# BCI_Module.net
KiCad netlist of a schematic drawn in EAGLE
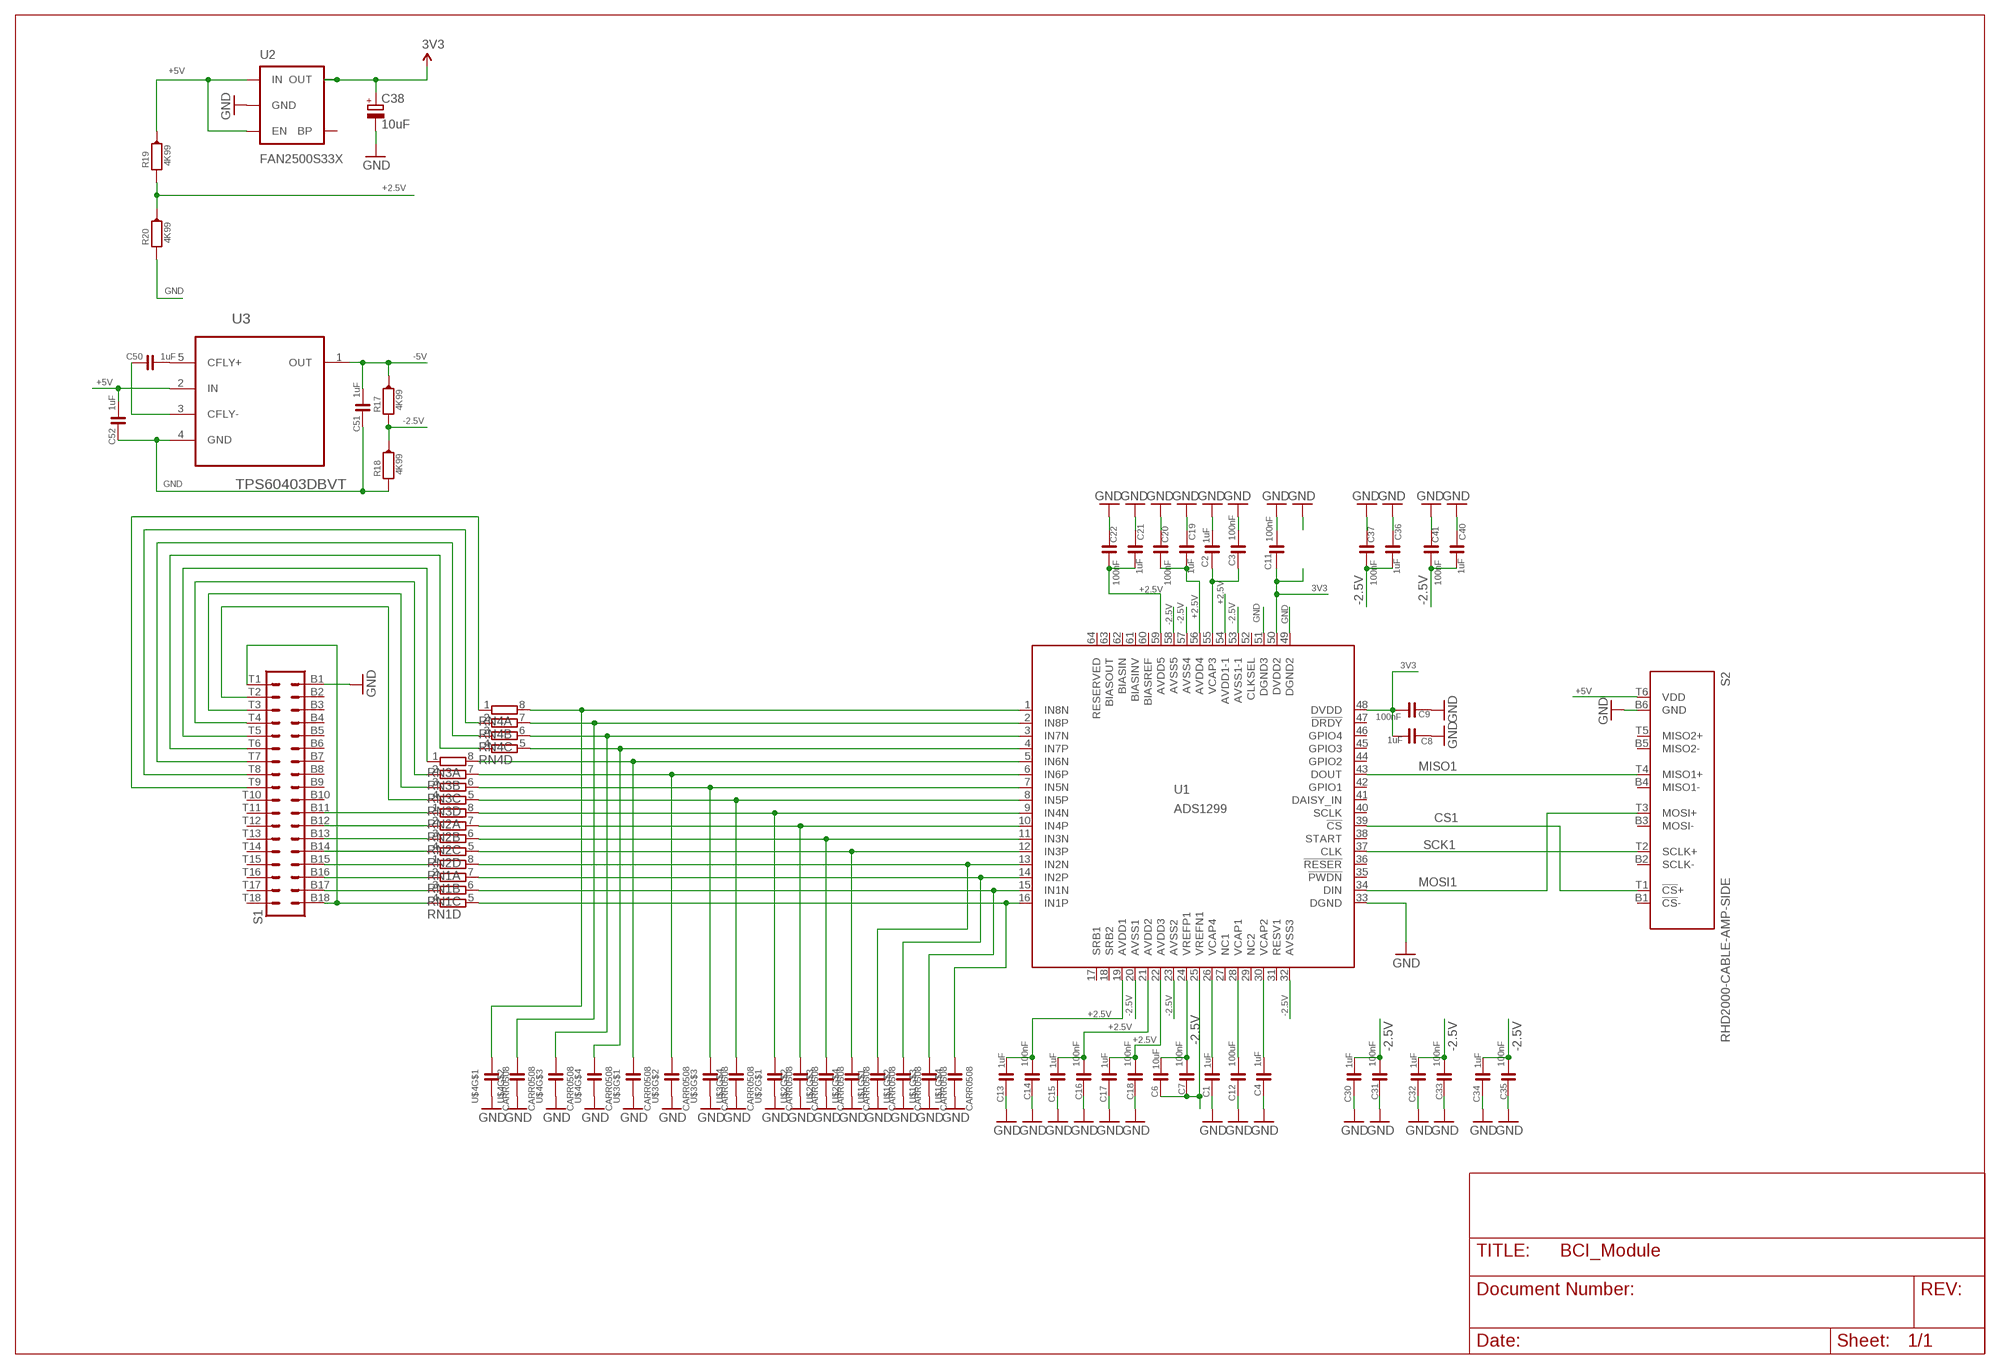
[diagram p0: schematic, sheet 1]

(export (version "E")
  (design (tool "Eeschema 10.0.6"))
  (components
    (comp (ref "C1")
      (value "1uF")
      (footprint "eagle-import:0603_R")
      (libsource (lib "eagle-import") (part "C0603_R"))
    )
    (comp (ref "C2")
      (value "1uF")
      (footprint "eagle-import:0603_R")
      (libsource (lib "eagle-import") (part "C0603_R"))
    )
    (comp (ref "C3")
      (value "100nF")
      (footprint "eagle-import:0402_R")
      (libsource (lib "eagle-import") (part "C0402_R"))
    )
    (comp (ref "C4")
      (value "1uF")
      (footprint "eagle-import:0603_R")
      (libsource (lib "eagle-import") (part "C0603_R"))
    )
    (comp (ref "C6")
      (value "10uF")
      (footprint "eagle-import:0603_R")
      (libsource (lib "eagle-import") (part "C0603_R"))
    )
    (comp (ref "C7")
      (value "100nF")
      (footprint "eagle-import:0402_R")
      (libsource (lib "eagle-import") (part "C0402_R"))
    )
    (comp (ref "C8")
      (value "1uF")
      (footprint "eagle-import:0603_R")
      (libsource (lib "eagle-import") (part "C0603_R"))
    )
    (comp (ref "C9")
      (value "100nF")
      (footprint "eagle-import:0402_R")
      (libsource (lib "eagle-import") (part "C0402_R"))
    )
    (comp (ref "C11")
      (value "100nF")
      (footprint "eagle-import:0402_R")
      (libsource (lib "eagle-import") (part "C0402_R"))
    )
    (comp (ref "C12")
      (value "100uF")
      (footprint "eagle-import:1206_R")
      (libsource (lib "eagle-import") (part "C1206_R"))
    )
    (comp (ref "C13")
      (value "1uF")
      (footprint "eagle-import:0603_R")
      (libsource (lib "eagle-import") (part "C0603_R"))
    )
    (comp (ref "C14")
      (value "100nF")
      (footprint "eagle-import:0402_R")
      (libsource (lib "eagle-import") (part "C0402_R"))
    )
    (comp (ref "C15")
      (value "1uF")
      (footprint "eagle-import:0603_R")
      (libsource (lib "eagle-import") (part "C0603_R"))
    )
    (comp (ref "C16")
      (value "100nF")
      (footprint "eagle-import:0402_R")
      (libsource (lib "eagle-import") (part "C0402_R"))
    )
    (comp (ref "C17")
      (value "1uF")
      (footprint "eagle-import:0603_R")
      (libsource (lib "eagle-import") (part "C0603_R"))
    )
    (comp (ref "C18")
      (value "100nF")
      (footprint "eagle-import:0402_R")
      (libsource (lib "eagle-import") (part "C0402_R"))
    )
    (comp (ref "C19")
      (value "1uF")
      (footprint "eagle-import:0603_R")
      (libsource (lib "eagle-import") (part "C0603_R"))
    )
    (comp (ref "C20")
      (value "100nF")
      (footprint "eagle-import:0402_R")
      (libsource (lib "eagle-import") (part "C0402_R"))
    )
    (comp (ref "C21")
      (value "1uF")
      (footprint "eagle-import:0603_R")
      (libsource (lib "eagle-import") (part "C0603_R"))
    )
    (comp (ref "C22")
      (value "100nF")
      (footprint "eagle-import:0402_R")
      (libsource (lib "eagle-import") (part "C0402_R"))
    )
    (comp (ref "C30")
      (value "1uF")
      (footprint "eagle-import:0603_R")
      (libsource (lib "eagle-import") (part "C0603_R"))
    )
    (comp (ref "C31")
      (value "100nF")
      (footprint "eagle-import:0402_R")
      (libsource (lib "eagle-import") (part "C0402_R"))
    )
    (comp (ref "C32")
      (value "1uF")
      (footprint "eagle-import:0603_R")
      (libsource (lib "eagle-import") (part "C0603_R"))
    )
    (comp (ref "C33")
      (value "100nF")
      (footprint "eagle-import:0402_R")
      (libsource (lib "eagle-import") (part "C0402_R"))
    )
    (comp (ref "C34")
      (value "1uF")
      (footprint "eagle-import:0603_R")
      (libsource (lib "eagle-import") (part "C0603_R"))
    )
    (comp (ref "C35")
      (value "100nF")
      (footprint "eagle-import:0402_R")
      (libsource (lib "eagle-import") (part "C0402_R"))
    )
    (comp (ref "C36")
      (value "1uF")
      (footprint "eagle-import:0603_R")
      (libsource (lib "eagle-import") (part "C0603_R"))
    )
    (comp (ref "C37")
      (value "100nF")
      (footprint "eagle-import:0402_R")
      (libsource (lib "eagle-import") (part "C0402_R"))
    )
    (comp (ref "C38")
      (value "10uF")
      (footprint "eagle-import:R_2012-12R")
      (libsource (lib "eagle-import") (part "CPOL-EUR/2012-12R"))
    )
    (comp (ref "C40")
      (value "1uF")
      (footprint "eagle-import:0603_R")
      (libsource (lib "eagle-import") (part "C0603_R"))
    )
    (comp (ref "C41")
      (value "100nF")
      (footprint "eagle-import:0402_R")
      (libsource (lib "eagle-import") (part "C0402_R"))
    )
    (comp (ref "C50")
      (value "1uF")
      (footprint "eagle-import:0603_R")
      (libsource (lib "eagle-import") (part "C0603_R"))
    )
    (comp (ref "C51")
      (value "1uF")
      (footprint "eagle-import:0603_R")
      (libsource (lib "eagle-import") (part "C0603_R"))
    )
    (comp (ref "C52")
      (value "1uF")
      (footprint "eagle-import:0603_R")
      (libsource (lib "eagle-import") (part "C0603_R"))
    )
    (comp (ref "R17")
      (value "4K99")
      (footprint "eagle-import:0402_R@1")
      (libsource (lib "eagle-import") (part "R0402_R"))
    )
    (comp (ref "R18")
      (value "4K99")
      (footprint "eagle-import:0402_R@1")
      (libsource (lib "eagle-import") (part "R0402_R"))
    )
    (comp (ref "R19")
      (value "4K99")
      (footprint "eagle-import:0402_R@1")
      (libsource (lib "eagle-import") (part "R0402_R"))
    )
    (comp (ref "R20")
      (value "4K99")
      (footprint "eagle-import:0402_R@1")
      (libsource (lib "eagle-import") (part "R0402_R"))
    )
    (comp (ref "RN1")
      (value "4R-NYC124")
      (footprint "eagle-import:YC124")
      (libsource (lib "eagle-import") (part "4R-NYC124"))
    )
    (comp (ref "RN2")
      (value "4R-NYC124")
      (footprint "eagle-import:YC124")
      (libsource (lib "eagle-import") (part "4R-NYC124"))
    )
    (comp (ref "RN3")
      (value "4R-NYC124")
      (footprint "eagle-import:YC124")
      (libsource (lib "eagle-import") (part "4R-NYC124"))
    )
    (comp (ref "RN4")
      (value "4R-NYC124")
      (footprint "eagle-import:YC124")
      (libsource (lib "eagle-import") (part "4R-NYC124"))
    )
    (comp (ref "S1")
      (value "OMNETICS_A79025")
      (footprint "eagle-import:OMNETICS_A79025")
      (libsource (lib "eagle-import") (part "OMNETICS_A79025"))
    )
    (comp (ref "S2")
      (value "RHD2000-CABLE-AMP-SIDE")
      (footprint "eagle-import:OMNETICS_PZN-12-AA")
      (libsource (lib "eagle-import") (part "RHD2000-CABLE-AMP-SIDE"))
    )
    (comp (ref "U$1")
      (value "CARR0508")
      (footprint "eagle-import:CARR0508")
      (libsource (lib "eagle-import") (part "CARR0508"))
    )
    (comp (ref "U$2")
      (value "CARR0508")
      (footprint "eagle-import:CARR0508")
      (libsource (lib "eagle-import") (part "CARR0508"))
    )
    (comp (ref "U$3")
      (value "CARR0508")
      (footprint "eagle-import:CARR0508")
      (libsource (lib "eagle-import") (part "CARR0508"))
    )
    (comp (ref "U$4")
      (value "CARR0508")
      (footprint "eagle-import:CARR0508")
      (libsource (lib "eagle-import") (part "CARR0508"))
    )
    (comp (ref "U1")
      (value "ADS1299")
      (footprint "eagle-import:SQFP-S-10X10-64")
      (libsource (lib "eagle-import") (part "ADS1299"))
    )
    (comp (ref "U2")
      (value "FAN2500S33X")
      (footprint "eagle-import:SOT23-5$2")
      (libsource (lib "eagle-import") (part "V_REG_LDOSMD"))
    )
    (comp (ref "U3")
      (value "TPS60403DBVT")
      (footprint "eagle-import:SOT95P280X145-5N")
      (libsource (lib "eagle-import") (part "TPS60403DBVT"))
    )
  )
  (nets
    (net (code "1") (name "/+2.5V") (class "Default")
      (node (ref "C13") (pin "1") (pinfunction "1_1") (pintype "bidirectional"))
      (node (ref "C14") (pin "1") (pinfunction "1_1") (pintype "bidirectional"))
      (node (ref "C15") (pin "1") (pinfunction "1_1") (pintype "bidirectional"))
      (node (ref "C16") (pin "1") (pinfunction "1_1") (pintype "bidirectional"))
      (node (ref "C17") (pin "1") (pinfunction "1_1") (pintype "bidirectional"))
      (node (ref "C18") (pin "1") (pinfunction "1_1") (pintype "bidirectional"))
      (node (ref "C19") (pin "1") (pinfunction "1_1") (pintype "bidirectional"))
      (node (ref "C20") (pin "1") (pinfunction "1_1") (pintype "bidirectional"))
      (node (ref "C21") (pin "1") (pinfunction "1_1") (pintype "bidirectional"))
      (node (ref "C22") (pin "1") (pinfunction "1_1") (pintype "bidirectional"))
      (node (ref "R19") (pin "2") (pinfunction "2_2") (pintype "bidirectional"))
      (node (ref "R20") (pin "1") (pinfunction "1_1") (pintype "bidirectional"))
      (node (ref "U1") (pin "19") (pinfunction "AVDD1_19") (pintype "output"))
      (node (ref "U1") (pin "21") (pinfunction "AVDD2_21") (pintype "power_in"))
      (node (ref "U1") (pin "22") (pinfunction "AVDD3_22") (pintype "power_in"))
      (node (ref "U1") (pin "54") (pinfunction "AVDD1-1_54") (pintype "power_in"))
      (node (ref "U1") (pin "56") (pinfunction "AVDD4_56") (pintype "input"))
      (node (ref "U1") (pin "59") (pinfunction "AVDD5_59") (pintype "power_in"))
    )
    (net (code "2") (name "/+5V") (class "Default")
      (node (ref "C52") (pin "1") (pinfunction "1_1") (pintype "bidirectional"))
      (node (ref "R19") (pin "1") (pinfunction "1_1") (pintype "bidirectional"))
      (node (ref "S2") (pin "T6") (pinfunction "VDD_T6") (pintype "bidirectional"))
      (node (ref "U2") (pin "1") (pinfunction "IN_1") (pintype "input"))
      (node (ref "U2") (pin "3") (pinfunction "EN_3") (pintype "input"))
      (node (ref "U3") (pin "2") (pinfunction "IN_2") (pintype "power_in"))
    )
    (net (code "3") (name "/-2.5V") (class "Default")
      (node (ref "C30") (pin "1") (pinfunction "1_1") (pintype "bidirectional"))
      (node (ref "C31") (pin "1") (pinfunction "1_1") (pintype "bidirectional"))
      (node (ref "C32") (pin "1") (pinfunction "1_1") (pintype "bidirectional"))
      (node (ref "C33") (pin "1") (pinfunction "1_1") (pintype "bidirectional"))
      (node (ref "C34") (pin "1") (pinfunction "1_1") (pintype "bidirectional"))
      (node (ref "C35") (pin "1") (pinfunction "1_1") (pintype "bidirectional"))
      (node (ref "C36") (pin "1") (pinfunction "1_1") (pintype "bidirectional"))
      (node (ref "C37") (pin "1") (pinfunction "1_1") (pintype "bidirectional"))
      (node (ref "C40") (pin "1") (pinfunction "1_1") (pintype "bidirectional"))
      (node (ref "C41") (pin "1") (pinfunction "1_1") (pintype "bidirectional"))
      (node (ref "C6") (pin "2") (pinfunction "2_2") (pintype "bidirectional"))
      (node (ref "C7") (pin "2") (pinfunction "2_2") (pintype "bidirectional"))
      (node (ref "R17") (pin "2") (pinfunction "2_2") (pintype "bidirectional"))
      (node (ref "R18") (pin "1") (pinfunction "1_1") (pintype "bidirectional"))
      (node (ref "U1") (pin "20") (pinfunction "AVSS1_20") (pintype "output"))
      (node (ref "U1") (pin "23") (pinfunction "AVSS2_23") (pintype "power_in"))
      (node (ref "U1") (pin "25") (pinfunction "VREFN1_25") (pintype "power_in"))
      (node (ref "U1") (pin "32") (pinfunction "AVSS3_32") (pintype "input"))
      (node (ref "U1") (pin "53") (pinfunction "AVSS1-1_53") (pintype "power_in"))
      (node (ref "U1") (pin "57") (pinfunction "AVSS4_57") (pintype "input"))
      (node (ref "U1") (pin "58") (pinfunction "AVSS5_58") (pintype "power_in"))
    )
    (net (code "4") (name "/-5V") (class "Default")
      (node (ref "C51") (pin "1") (pinfunction "1_1") (pintype "bidirectional"))
      (node (ref "R17") (pin "1") (pinfunction "1_1") (pintype "bidirectional"))
      (node (ref "U3") (pin "1") (pinfunction "OUT_1") (pintype "output"))
    )
    (net (code "5") (name "/BIASREF") (class "Default")
      (node (ref "U1") (pin "60") (pinfunction "BIASREF_60") (pintype "power_in"))
    )
    (net (code "6") (name "/CS1") (class "Default")
      (node (ref "S2") (pin "T1") (pinfunction "~{CS}+_T1") (pintype "bidirectional"))
      (node (ref "U1") (pin "39") (pinfunction "~{CS}_39") (pintype "input"))
    )
    (net (code "7") (name "/GPIO2") (class "Default")
      (node (ref "U1") (pin "44") (pinfunction "GPIO2_44") (pintype "power_in"))
    )
    (net (code "8") (name "/MISO1") (class "Default")
      (node (ref "S2") (pin "T4") (pinfunction "MISO1+_T4") (pintype "bidirectional"))
      (node (ref "U1") (pin "43") (pinfunction "DOUT_43") (pintype "power_in"))
    )
    (net (code "9") (name "/MOSI1") (class "Default")
      (node (ref "S2") (pin "T3") (pinfunction "MOSI+_T3") (pintype "bidirectional"))
      (node (ref "U1") (pin "34") (pinfunction "DIN_34") (pintype "input"))
    )
    (net (code "10") (name "/SCK1") (class "Default")
      (node (ref "S2") (pin "T2") (pinfunction "SCLK+_T2") (pintype "bidirectional"))
      (node (ref "U1") (pin "37") (pinfunction "CLK_37") (pintype "input"))
    )
    (net (code "11") (name "3V3") (class "Default")
      (node (ref "C11") (pin "1") (pinfunction "1_1") (pintype "bidirectional"))
      (node (ref "C38") (pin "+") (pinfunction "+_+") (pintype "passive"))
      (node (ref "C8") (pin "1") (pinfunction "1_1") (pintype "bidirectional"))
      (node (ref "C9") (pin "1") (pinfunction "1_1") (pintype "bidirectional"))
      (node (ref "U1") (pin "48") (pinfunction "DVDD_48") (pintype "input"))
      (node (ref "U1") (pin "50") (pinfunction "DVDD2_50") (pintype "input"))
      (node (ref "U2") (pin "5") (pinfunction "OUT_5") (pintype "passive"))
    )
    (net (code "12") (name "GND") (class "Default")
      (node (ref "C1") (pin "2") (pinfunction "2_2") (pintype "bidirectional"))
      (node (ref "C11") (pin "2") (pinfunction "2_2") (pintype "bidirectional"))
      (node (ref "C12") (pin "2") (pinfunction "2_2") (pintype "bidirectional"))
      (node (ref "C13") (pin "2") (pinfunction "2_2") (pintype "bidirectional"))
      (node (ref "C14") (pin "2") (pinfunction "2_2") (pintype "bidirectional"))
      (node (ref "C15") (pin "2") (pinfunction "2_2") (pintype "bidirectional"))
      (node (ref "C16") (pin "2") (pinfunction "2_2") (pintype "bidirectional"))
      (node (ref "C17") (pin "2") (pinfunction "2_2") (pintype "bidirectional"))
      (node (ref "C18") (pin "2") (pinfunction "2_2") (pintype "bidirectional"))
      (node (ref "C19") (pin "2") (pinfunction "2_2") (pintype "bidirectional"))
      (node (ref "C2") (pin "2") (pinfunction "2_2") (pintype "bidirectional"))
      (node (ref "C20") (pin "2") (pinfunction "2_2") (pintype "bidirectional"))
      (node (ref "C21") (pin "2") (pinfunction "2_2") (pintype "bidirectional"))
      (node (ref "C22") (pin "2") (pinfunction "2_2") (pintype "bidirectional"))
      (node (ref "C3") (pin "2") (pinfunction "2_2") (pintype "bidirectional"))
      (node (ref "C30") (pin "2") (pinfunction "2_2") (pintype "bidirectional"))
      (node (ref "C31") (pin "2") (pinfunction "2_2") (pintype "bidirectional"))
      (node (ref "C32") (pin "2") (pinfunction "2_2") (pintype "bidirectional"))
      (node (ref "C33") (pin "2") (pinfunction "2_2") (pintype "bidirectional"))
      (node (ref "C34") (pin "2") (pinfunction "2_2") (pintype "bidirectional"))
      (node (ref "C35") (pin "2") (pinfunction "2_2") (pintype "bidirectional"))
      (node (ref "C36") (pin "2") (pinfunction "2_2") (pintype "bidirectional"))
      (node (ref "C37") (pin "2") (pinfunction "2_2") (pintype "bidirectional"))
      (node (ref "C38") (pin "-") (pinfunction "-_-") (pintype "passive"))
      (node (ref "C4") (pin "2") (pinfunction "2_2") (pintype "bidirectional"))
      (node (ref "C40") (pin "2") (pinfunction "2_2") (pintype "bidirectional"))
      (node (ref "C41") (pin "2") (pinfunction "2_2") (pintype "bidirectional"))
      (node (ref "C51") (pin "2") (pinfunction "2_2") (pintype "bidirectional"))
      (node (ref "C52") (pin "2") (pinfunction "2_2") (pintype "bidirectional"))
      (node (ref "C8") (pin "2") (pinfunction "2_2") (pintype "bidirectional"))
      (node (ref "C9") (pin "2") (pinfunction "2_2") (pintype "bidirectional"))
      (node (ref "R18") (pin "2") (pinfunction "2_2") (pintype "bidirectional"))
      (node (ref "R20") (pin "2") (pinfunction "2_2") (pintype "bidirectional"))
      (node (ref "S1") (pin "B1") (pinfunction "B1_B1") (pintype "passive"))
      (node (ref "S2") (pin "B6") (pinfunction "GND_B6") (pintype "power_in"))
      (node (ref "U$1") (pin "P$2") (pinfunction "2_P$2") (pintype "bidirectional"))
      (node (ref "U$1") (pin "P$4") (pinfunction "2_P$4") (pintype "bidirectional"))
      (node (ref "U$1") (pin "P$6") (pinfunction "2_P$6") (pintype "bidirectional"))
      (node (ref "U$1") (pin "P$8") (pinfunction "2_P$8") (pintype "bidirectional"))
      (node (ref "U$2") (pin "P$2") (pinfunction "2_P$2") (pintype "bidirectional"))
      (node (ref "U$2") (pin "P$4") (pinfunction "2_P$4") (pintype "bidirectional"))
      (node (ref "U$2") (pin "P$6") (pinfunction "2_P$6") (pintype "bidirectional"))
      (node (ref "U$2") (pin "P$8") (pinfunction "2_P$8") (pintype "bidirectional"))
      (node (ref "U$3") (pin "P$2") (pinfunction "2_P$2") (pintype "bidirectional"))
      (node (ref "U$3") (pin "P$4") (pinfunction "2_P$4") (pintype "bidirectional"))
      (node (ref "U$3") (pin "P$6") (pinfunction "2_P$6") (pintype "bidirectional"))
      (node (ref "U$3") (pin "P$8") (pinfunction "2_P$8") (pintype "bidirectional"))
      (node (ref "U$4") (pin "P$2") (pinfunction "2_P$2") (pintype "bidirectional"))
      (node (ref "U$4") (pin "P$4") (pinfunction "2_P$4") (pintype "bidirectional"))
      (node (ref "U$4") (pin "P$6") (pinfunction "2_P$6") (pintype "bidirectional"))
      (node (ref "U$4") (pin "P$8") (pinfunction "2_P$8") (pintype "bidirectional"))
      (node (ref "U1") (pin "33") (pinfunction "DGND_33") (pintype "input"))
      (node (ref "U1") (pin "49") (pinfunction "DGND2_49") (pintype "input"))
      (node (ref "U1") (pin "51") (pinfunction "DGND3_51") (pintype "input"))
      (node (ref "U2") (pin "2") (pinfunction "GND_2") (pintype "input"))
      (node (ref "U3") (pin "4") (pinfunction "GND_4") (pintype "passive"))
    )
    (net (code "13") (name "Net-(RN1-Pad1)") (class "Default")
      (node (ref "RN1") (pin "1") (pinfunction "1_1") (pintype "passive"))
      (node (ref "S1") (pin "B15") (pinfunction "B15_B15") (pintype "passive"))
    )
    (net (code "14") (name "Net-(RN1A-2)") (class "Default")
      (node (ref "RN1") (pin "8") (pinfunction "2_8") (pintype "passive"))
      (node (ref "U$1") (pin "P$1") (pinfunction "1_P$1") (pintype "bidirectional"))
      (node (ref "U1") (pin "13") (pinfunction "IN2N_13") (pintype "output"))
    )
    (net (code "15") (name "Net-(RN1B-1)") (class "Default")
      (node (ref "RN1") (pin "2") (pinfunction "1_2") (pintype "passive"))
      (node (ref "S1") (pin "B16") (pinfunction "B16_B16") (pintype "passive"))
    )
    (net (code "16") (name "Net-(RN1B-2)") (class "Default")
      (node (ref "RN1") (pin "7") (pinfunction "2_7") (pintype "passive"))
      (node (ref "U$1") (pin "P$3") (pinfunction "1_P$3") (pintype "bidirectional"))
      (node (ref "U1") (pin "14") (pinfunction "IN2P_14") (pintype "output"))
    )
    (net (code "17") (name "Net-(RN1C-1)") (class "Default")
      (node (ref "RN1") (pin "3") (pinfunction "1_3") (pintype "passive"))
      (node (ref "S1") (pin "B17") (pinfunction "B17_B17") (pintype "passive"))
    )
    (net (code "18") (name "Net-(RN1C-2)") (class "Default")
      (node (ref "RN1") (pin "6") (pinfunction "2_6") (pintype "passive"))
      (node (ref "U$1") (pin "P$5") (pinfunction "1_P$5") (pintype "bidirectional"))
      (node (ref "U1") (pin "15") (pinfunction "IN1N_15") (pintype "output"))
    )
    (net (code "19") (name "Net-(RN1D-1)") (class "Default")
      (node (ref "RN1") (pin "4") (pinfunction "1_4") (pintype "passive"))
      (node (ref "S1") (pin "B18") (pinfunction "B18_B18") (pintype "passive"))
      (node (ref "S1") (pin "T1") (pinfunction "T1_T1") (pintype "passive"))
    )
    (net (code "20") (name "Net-(RN1D-2)") (class "Default")
      (node (ref "RN1") (pin "5") (pinfunction "2_5") (pintype "passive"))
      (node (ref "U$1") (pin "P$7") (pinfunction "1_P$7") (pintype "bidirectional"))
      (node (ref "U1") (pin "16") (pinfunction "IN1P_16") (pintype "output"))
    )
    (net (code "21") (name "Net-(RN2-Pad1)") (class "Default")
      (node (ref "RN2") (pin "1") (pinfunction "1_1") (pintype "passive"))
      (node (ref "S1") (pin "B11") (pinfunction "B11_B11") (pintype "passive"))
    )
    (net (code "22") (name "Net-(RN2A-2)") (class "Default")
      (node (ref "RN2") (pin "8") (pinfunction "2_8") (pintype "passive"))
      (node (ref "U$2") (pin "P$1") (pinfunction "1_P$1") (pintype "bidirectional"))
      (node (ref "U1") (pin "9") (pinfunction "IN4N_9") (pintype "input"))
    )
    (net (code "23") (name "Net-(RN2B-1)") (class "Default")
      (node (ref "RN2") (pin "2") (pinfunction "1_2") (pintype "passive"))
      (node (ref "S1") (pin "B12") (pinfunction "B12_B12") (pintype "passive"))
    )
    (net (code "24") (name "Net-(RN2B-2)") (class "Default")
      (node (ref "RN2") (pin "7") (pinfunction "2_7") (pintype "passive"))
      (node (ref "U$2") (pin "P$3") (pinfunction "1_P$3") (pintype "bidirectional"))
      (node (ref "U1") (pin "10") (pinfunction "IN4P_10") (pintype "input"))
    )
    (net (code "25") (name "Net-(RN2C-1)") (class "Default")
      (node (ref "RN2") (pin "3") (pinfunction "1_3") (pintype "passive"))
      (node (ref "S1") (pin "B13") (pinfunction "B13_B13") (pintype "passive"))
    )
    (net (code "26") (name "Net-(RN2C-2)") (class "Default")
      (node (ref "RN2") (pin "6") (pinfunction "2_6") (pintype "passive"))
      (node (ref "U$2") (pin "P$5") (pinfunction "1_P$5") (pintype "bidirectional"))
      (node (ref "U1") (pin "11") (pinfunction "IN3N_11") (pintype "input"))
    )
    (net (code "27") (name "Net-(RN2D-1)") (class "Default")
      (node (ref "RN2") (pin "4") (pinfunction "1_4") (pintype "passive"))
      (node (ref "S1") (pin "B14") (pinfunction "B14_B14") (pintype "passive"))
    )
    (net (code "28") (name "Net-(RN2D-2)") (class "Default")
      (node (ref "RN2") (pin "5") (pinfunction "2_5") (pintype "passive"))
      (node (ref "U$2") (pin "P$7") (pinfunction "1_P$7") (pintype "bidirectional"))
      (node (ref "U1") (pin "12") (pinfunction "IN3P_12") (pintype "input"))
    )
    (net (code "29") (name "Net-(RN3-Pad1)") (class "Default")
      (node (ref "RN3") (pin "1") (pinfunction "1_1") (pintype "passive"))
      (node (ref "S1") (pin "T5") (pinfunction "T5_T5") (pintype "passive"))
    )
    (net (code "30") (name "Net-(RN3A-2)") (class "Default")
      (node (ref "RN3") (pin "8") (pinfunction "2_8") (pintype "passive"))
      (node (ref "U$3") (pin "P$1") (pinfunction "1_P$1") (pintype "bidirectional"))
      (node (ref "U1") (pin "5") (pinfunction "IN6N_5") (pintype "power_in"))
    )
    (net (code "31") (name "Net-(RN3B-1)") (class "Default")
      (node (ref "RN3") (pin "2") (pinfunction "1_2") (pintype "passive"))
      (node (ref "S1") (pin "T4") (pinfunction "T4_T4") (pintype "passive"))
    )
    (net (code "32") (name "Net-(RN3B-2)") (class "Default")
      (node (ref "RN3") (pin "7") (pinfunction "2_7") (pintype "passive"))
      (node (ref "U$3") (pin "P$3") (pinfunction "1_P$3") (pintype "bidirectional"))
      (node (ref "U1") (pin "6") (pinfunction "IN6P_6") (pintype "power_in"))
    )
    (net (code "33") (name "Net-(RN3C-1)") (class "Default")
      (node (ref "RN3") (pin "3") (pinfunction "1_3") (pintype "passive"))
      (node (ref "S1") (pin "T3") (pinfunction "T3_T3") (pintype "passive"))
    )
    (net (code "34") (name "Net-(RN3C-2)") (class "Default")
      (node (ref "RN3") (pin "6") (pinfunction "2_6") (pintype "passive"))
      (node (ref "U$3") (pin "P$5") (pinfunction "1_P$5") (pintype "bidirectional"))
      (node (ref "U1") (pin "7") (pinfunction "IN5N_7") (pintype "power_in"))
    )
    (net (code "35") (name "Net-(RN3D-1)") (class "Default")
      (node (ref "RN3") (pin "4") (pinfunction "1_4") (pintype "passive"))
      (node (ref "S1") (pin "T2") (pinfunction "T2_T2") (pintype "passive"))
    )
    (net (code "36") (name "Net-(RN3D-2)") (class "Default")
      (node (ref "RN3") (pin "5") (pinfunction "2_5") (pintype "passive"))
      (node (ref "U$3") (pin "P$7") (pinfunction "1_P$7") (pintype "bidirectional"))
      (node (ref "U1") (pin "8") (pinfunction "IN5P_8") (pintype "input"))
    )
    (net (code "37") (name "Net-(RN4-Pad1)") (class "Default")
      (node (ref "RN4") (pin "1") (pinfunction "1_1") (pintype "passive"))
      (node (ref "S1") (pin "T9") (pinfunction "T9_T9") (pintype "passive"))
    )
    (net (code "38") (name "Net-(RN4A-2)") (class "Default")
      (node (ref "RN4") (pin "8") (pinfunction "2_8") (pintype "passive"))
      (node (ref "U$4") (pin "P$1") (pinfunction "1_P$1") (pintype "bidirectional"))
      (node (ref "U1") (pin "1") (pinfunction "IN8N_1") (pintype "input"))
    )
    (net (code "39") (name "Net-(RN4B-1)") (class "Default")
      (node (ref "RN4") (pin "2") (pinfunction "1_2") (pintype "passive"))
      (node (ref "S1") (pin "T8") (pinfunction "T8_T8") (pintype "passive"))
    )
    (net (code "40") (name "Net-(RN4B-2)") (class "Default")
      (node (ref "RN4") (pin "7") (pinfunction "2_7") (pintype "passive"))
      (node (ref "U$4") (pin "P$3") (pinfunction "1_P$3") (pintype "bidirectional"))
      (node (ref "U1") (pin "2") (pinfunction "IN8P_2") (pintype "input"))
    )
    (net (code "41") (name "Net-(RN4C-1)") (class "Default")
      (node (ref "RN4") (pin "3") (pinfunction "1_3") (pintype "passive"))
      (node (ref "S1") (pin "T7") (pinfunction "T7_T7") (pintype "passive"))
    )
    (net (code "42") (name "Net-(RN4C-2)") (class "Default")
      (node (ref "RN4") (pin "6") (pinfunction "2_6") (pintype "passive"))
      (node (ref "U$4") (pin "P$5") (pinfunction "1_P$5") (pintype "bidirectional"))
      (node (ref "U1") (pin "3") (pinfunction "IN7N_3") (pintype "input"))
    )
    (net (code "43") (name "Net-(RN4D-1)") (class "Default")
      (node (ref "RN4") (pin "4") (pinfunction "1_4") (pintype "passive"))
      (node (ref "S1") (pin "T6") (pinfunction "T6_T6") (pintype "passive"))
    )
    (net (code "44") (name "Net-(RN4D-2)") (class "Default")
      (node (ref "RN4") (pin "5") (pinfunction "2_5") (pintype "passive"))
      (node (ref "U$4") (pin "P$7") (pinfunction "1_P$7") (pintype "bidirectional"))
      (node (ref "U1") (pin "4") (pinfunction "IN7P_4") (pintype "input"))
    )
    (net (code "45") (name "Net-(U1-VCAP1)") (class "Default")
      (node (ref "C12") (pin "1") (pinfunction "1_1") (pintype "bidirectional"))
      (node (ref "U1") (pin "28") (pinfunction "VCAP1_28") (pintype "bidirectional"))
    )
    (net (code "46") (name "Net-(U1-VCAP2)") (class "Default")
      (node (ref "C4") (pin "1") (pinfunction "1_1") (pintype "bidirectional"))
      (node (ref "U1") (pin "30") (pinfunction "VCAP2_30") (pintype "input"))
    )
    (net (code "47") (name "Net-(U1-VCAP3)") (class "Default")
      (node (ref "C2") (pin "1") (pinfunction "1_1") (pintype "bidirectional"))
      (node (ref "C3") (pin "1") (pinfunction "1_1") (pintype "bidirectional"))
      (node (ref "U1") (pin "55") (pinfunction "VCAP3_55") (pintype "output"))
    )
    (net (code "48") (name "Net-(U1-VCAP4)") (class "Default")
      (node (ref "C1") (pin "1") (pinfunction "1_1") (pintype "bidirectional"))
      (node (ref "U1") (pin "26") (pinfunction "VCAP4_26") (pintype "power_in"))
    )
    (net (code "49") (name "Net-(U1-VREFP1)") (class "Default")
      (node (ref "C6") (pin "1") (pinfunction "1_1") (pintype "bidirectional"))
      (node (ref "C7") (pin "1") (pinfunction "1_1") (pintype "bidirectional"))
      (node (ref "U1") (pin "24") (pinfunction "VREFP1_24") (pintype "power_in"))
    )
    (net (code "50") (name "Net-(U3-CFLY+)") (class "Default")
      (node (ref "C50") (pin "1") (pinfunction "1_1") (pintype "bidirectional"))
      (node (ref "U3") (pin "5") (pinfunction "CFLY+_5") (pintype "input"))
    )
    (net (code "51") (name "Net-(U3-CFLY-)") (class "Default")
      (node (ref "C50") (pin "2") (pinfunction "2_2") (pintype "bidirectional"))
      (node (ref "U3") (pin "3") (pinfunction "CFLY-_3") (pintype "input"))
    )
    (net (code "52") (name "unconnected-(S1-PadB2)") (class "Default")
      (node (ref "S1") (pin "B2") (pinfunction "B2_B2") (pintype "passive"))
    )
    (net (code "53") (name "unconnected-(S1-PadB3)") (class "Default")
      (node (ref "S1") (pin "B3") (pinfunction "B3_B3") (pintype "passive"))
    )
    (net (code "54") (name "unconnected-(S1-PadB4)") (class "Default")
      (node (ref "S1") (pin "B4") (pinfunction "B4_B4") (pintype "passive"))
    )
    (net (code "55") (name "unconnected-(S1-PadB5)") (class "Default")
      (node (ref "S1") (pin "B5") (pinfunction "B5_B5") (pintype "passive"))
    )
    (net (code "56") (name "unconnected-(S1-PadB6)") (class "Default")
      (node (ref "S1") (pin "B6") (pinfunction "B6_B6") (pintype "passive"))
    )
    (net (code "57") (name "unconnected-(S1-PadB7)") (class "Default")
      (node (ref "S1") (pin "B7") (pinfunction "B7_B7") (pintype "passive"))
    )
    (net (code "58") (name "unconnected-(S1-PadB8)") (class "Default")
      (node (ref "S1") (pin "B8") (pinfunction "B8_B8") (pintype "passive"))
    )
    (net (code "59") (name "unconnected-(S1-PadB9)") (class "Default")
      (node (ref "S1") (pin "B9") (pinfunction "B9_B9") (pintype "passive"))
    )
    (net (code "60") (name "unconnected-(S1-PadB10)") (class "Default")
      (node (ref "S1") (pin "B10") (pinfunction "B10_B10") (pintype "passive"))
    )
    (net (code "61") (name "unconnected-(S1-PadT10)") (class "Default")
      (node (ref "S1") (pin "T10") (pinfunction "T10_T10") (pintype "passive"))
    )
    (net (code "62") (name "unconnected-(S1-PadT11)") (class "Default")
      (node (ref "S1") (pin "T11") (pinfunction "T11_T11") (pintype "passive"))
    )
    (net (code "63") (name "unconnected-(S1-PadT12)") (class "Default")
      (node (ref "S1") (pin "T12") (pinfunction "T12_T12") (pintype "passive"))
    )
    (net (code "64") (name "unconnected-(S1-PadT13)") (class "Default")
      (node (ref "S1") (pin "T13") (pinfunction "T13_T13") (pintype "passive"))
    )
    (net (code "65") (name "unconnected-(S1-PadT14)") (class "Default")
      (node (ref "S1") (pin "T14") (pinfunction "T14_T14") (pintype "passive"))
    )
    (net (code "66") (name "unconnected-(S1-PadT15)") (class "Default")
      (node (ref "S1") (pin "T15") (pinfunction "T15_T15") (pintype "passive"))
    )
    (net (code "67") (name "unconnected-(S1-PadT16)") (class "Default")
      (node (ref "S1") (pin "T16") (pinfunction "T16_T16") (pintype "passive"))
    )
    (net (code "68") (name "unconnected-(S1-PadT17)") (class "Default")
      (node (ref "S1") (pin "T17") (pinfunction "T17_T17") (pintype "passive"))
    )
    (net (code "69") (name "unconnected-(S1-PadT18)") (class "Default")
      (node (ref "S1") (pin "T18") (pinfunction "T18_T18") (pintype "passive"))
    )
    (net (code "70") (name "unconnected-(S2-MISO1--PadB4)") (class "Default")
      (node (ref "S2") (pin "B4") (pinfunction "MISO1-_B4") (pintype "bidirectional"))
    )
    (net (code "71") (name "unconnected-(S2-MISO2+-PadT5)") (class "Default")
      (node (ref "S2") (pin "T5") (pinfunction "MISO2+_T5") (pintype "bidirectional"))
    )
    (net (code "72") (name "unconnected-(S2-MISO2--PadB5)") (class "Default")
      (node (ref "S2") (pin "B5") (pinfunction "MISO2-_B5") (pintype "bidirectional"))
    )
    (net (code "73") (name "unconnected-(S2-MOSI--PadB3)") (class "Default")
      (node (ref "S2") (pin "B3") (pinfunction "MOSI-_B3") (pintype "bidirectional"))
    )
    (net (code "74") (name "unconnected-(S2-SCLK--PadB2)") (class "Default")
      (node (ref "S2") (pin "B2") (pinfunction "SCLK-_B2") (pintype "bidirectional"))
    )
    (net (code "75") (name "unconnected-(S2-~{CS}--PadB1)") (class "Default")
      (node (ref "S2") (pin "B1") (pinfunction "~{CS}-_B1") (pintype "bidirectional"))
    )
    (net (code "76") (name "unconnected-(U1-BIASIN-Pad62)") (class "Default")
      (node (ref "U1") (pin "62") (pinfunction "BIASIN_62") (pintype "input"))
    )
    (net (code "77") (name "unconnected-(U1-BIASINV-Pad61)") (class "Default")
      (node (ref "U1") (pin "61") (pinfunction "BIASINV_61") (pintype "input"))
    )
    (net (code "78") (name "unconnected-(U1-BIASOUT-Pad63)") (class "Default")
      (node (ref "U1") (pin "63") (pinfunction "BIASOUT_63") (pintype "input"))
    )
    (net (code "79") (name "unconnected-(U1-CLKSEL-Pad52)") (class "Default")
      (node (ref "U1") (pin "52") (pinfunction "CLKSEL_52") (pintype "input"))
    )
    (net (code "80") (name "unconnected-(U1-DAISY_IN-Pad41)") (class "Default")
      (node (ref "U1") (pin "41") (pinfunction "DAISY_IN_41") (pintype "input"))
    )
    (net (code "81") (name "unconnected-(U1-GPIO1-Pad42)") (class "Default")
      (node (ref "U1") (pin "42") (pinfunction "GPIO1_42") (pintype "input"))
    )
    (net (code "82") (name "unconnected-(U1-GPIO3-Pad45)") (class "Default")
      (node (ref "U1") (pin "45") (pinfunction "GPIO3_45") (pintype "input"))
    )
    (net (code "83") (name "unconnected-(U1-GPIO4-Pad46)") (class "Default")
      (node (ref "U1") (pin "46") (pinfunction "GPIO4_46") (pintype "input"))
    )
    (net (code "84") (name "unconnected-(U1-NC1-Pad27)") (class "Default")
      (node (ref "U1") (pin "27") (pinfunction "NC1_27") (pintype "input"))
    )
    (net (code "85") (name "unconnected-(U1-NC2-Pad29)") (class "Default")
      (node (ref "U1") (pin "29") (pinfunction "NC2_29") (pintype "bidirectional"))
    )
    (net (code "86") (name "unconnected-(U1-RESERVED-Pad64)") (class "Default")
      (node (ref "U1") (pin "64") (pinfunction "RESERVED_64") (pintype "input"))
    )
    (net (code "87") (name "unconnected-(U1-RESV1-Pad31)") (class "Default")
      (node (ref "U1") (pin "31") (pinfunction "RESV1_31") (pintype "input"))
    )
    (net (code "88") (name "unconnected-(U1-SCLK-Pad40)") (class "Default")
      (node (ref "U1") (pin "40") (pinfunction "SCLK_40") (pintype "input"))
    )
    (net (code "89") (name "unconnected-(U1-SRB1-Pad17)") (class "Default")
      (node (ref "U1") (pin "17") (pinfunction "SRB1_17") (pintype "output"))
    )
    (net (code "90") (name "unconnected-(U1-SRB2-Pad18)") (class "Default")
      (node (ref "U1") (pin "18") (pinfunction "SRB2_18") (pintype "output"))
    )
    (net (code "91") (name "unconnected-(U1-START-Pad38)") (class "Default")
      (node (ref "U1") (pin "38") (pinfunction "START_38") (pintype "input"))
    )
    (net (code "92") (name "unconnected-(U1-~{DRDY}-Pad47)") (class "Default")
      (node (ref "U1") (pin "47") (pinfunction "~{DRDY}_47") (pintype "input"))
    )
    (net (code "93") (name "unconnected-(U1-~{PWDN}-Pad35)") (class "Default")
      (node (ref "U1") (pin "35") (pinfunction "~{PWDN}_35") (pintype "input"))
    )
    (net (code "94") (name "unconnected-(U1-~{RESER}-Pad36)") (class "Default")
      (node (ref "U1") (pin "36") (pinfunction "~{RESER}_36") (pintype "input"))
    )
    (net (code "95") (name "unconnected-(U2-BP-Pad4)") (class "Default")
      (node (ref "U2") (pin "4") (pinfunction "BP_4") (pintype "input"))
    )
  )
)
